# Ex_9BlueLed1RedLedPanel.net
KiCad netlist of a schematic drawn in EAGLE
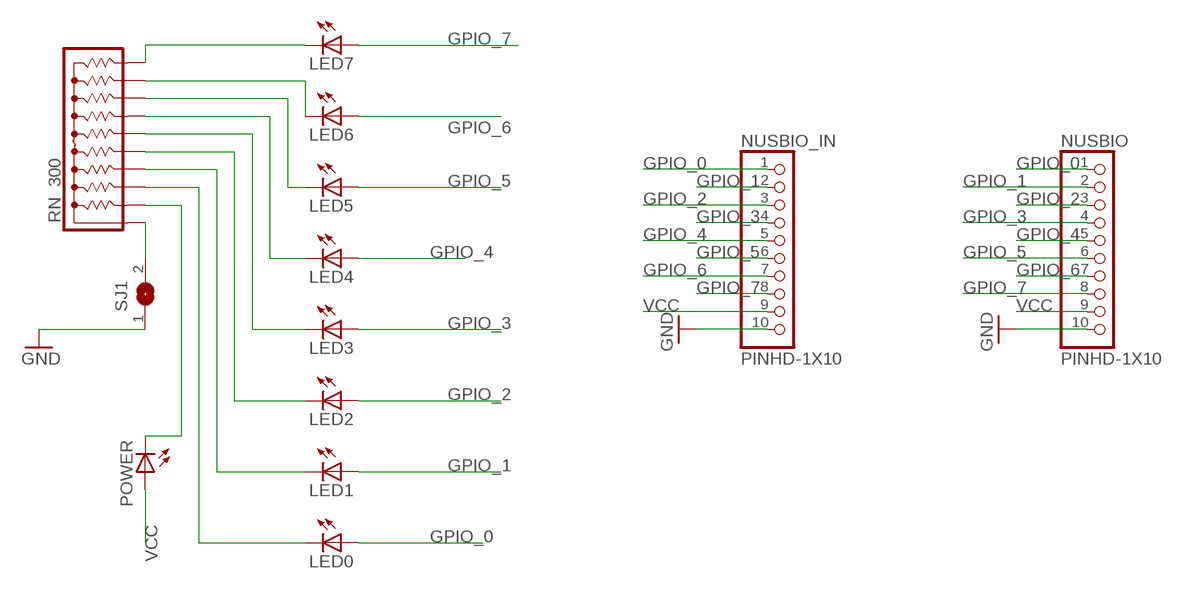
[diagram p0: schematic, sheet 1]

(export (version "E")
  (design (tool "Eeschema 10.0.6"))
  (components
    (comp (ref "LED0")
      (value "LEDSMT1206")
      (footprint "eagle-import:1206")
      (libsource (lib "eagle-import") (part "LEDSMT1206"))
    )
    (comp (ref "LED1")
      (value "LEDSMT1206")
      (footprint "eagle-import:1206")
      (libsource (lib "eagle-import") (part "LEDSMT1206"))
    )
    (comp (ref "LED2")
      (value "LEDSMT1206")
      (footprint "eagle-import:1206")
      (libsource (lib "eagle-import") (part "LEDSMT1206"))
    )
    (comp (ref "LED3")
      (value "LEDSMT1206")
      (footprint "eagle-import:1206")
      (libsource (lib "eagle-import") (part "LEDSMT1206"))
    )
    (comp (ref "LED4")
      (value "LEDSMT1206")
      (footprint "eagle-import:1206")
      (libsource (lib "eagle-import") (part "LEDSMT1206"))
    )
    (comp (ref "LED5")
      (value "LEDSMT1206")
      (footprint "eagle-import:1206")
      (libsource (lib "eagle-import") (part "LEDSMT1206"))
    )
    (comp (ref "LED6")
      (value "LEDSMT1206")
      (footprint "eagle-import:1206")
      (libsource (lib "eagle-import") (part "LEDSMT1206"))
    )
    (comp (ref "LED7")
      (value "LEDSMT1206")
      (footprint "eagle-import:1206")
      (libsource (lib "eagle-import") (part "LEDSMT1206"))
    )
    (comp (ref "NUSBIO")
      (value "PINHD-1X10")
      (footprint "eagle-import:1X10-BIG")
      (libsource (lib "eagle-import") (part "PINHD-1X10"))
    )
    (comp (ref "NUSBIO_IN")
      (value "PINHD-1X10")
      (footprint "eagle-import:1X10-BIG")
      (libsource (lib "eagle-import") (part "PINHD-1X10"))
    )
    (comp (ref "POWER")
      (value "LEDSMT1206")
      (footprint "eagle-import:1206")
      (libsource (lib "eagle-import") (part "LEDSMT1206"))
    )
    (comp (ref "RN_300")
      (value "4610X")
      (footprint "eagle-import:SIP10")
      (libsource (lib "eagle-import") (part "4610X"))
    )
    (comp (ref "SJ1")
      (value "SOLDERJUMPERREFLOW_NOPASTE")
      (footprint "eagle-import:SOLDERJUMPER_REFLOW_NOPASTE")
      (libsource (lib "eagle-import") (part "SOLDERJUMPERREFLOW_NOPASTE"))
    )
  )
  (nets
    (net (code "1") (name "/GPIO_0") (class "Default")
      (node (ref "LED0") (pin "A") (pinfunction "A_A") (pintype "passive"))
      (node (ref "NUSBIO") (pin "1") (pinfunction "1_1") (pintype "passive"))
      (node (ref "NUSBIO_IN") (pin "1") (pinfunction "1_1") (pintype "passive"))
    )
    (net (code "2") (name "/GPIO_1") (class "Default")
      (node (ref "LED1") (pin "A") (pinfunction "A_A") (pintype "passive"))
      (node (ref "NUSBIO") (pin "2") (pinfunction "2_2") (pintype "passive"))
      (node (ref "NUSBIO_IN") (pin "2") (pinfunction "2_2") (pintype "passive"))
    )
    (net (code "3") (name "/GPIO_2") (class "Default")
      (node (ref "LED2") (pin "A") (pinfunction "A_A") (pintype "passive"))
      (node (ref "NUSBIO") (pin "3") (pinfunction "3_3") (pintype "passive"))
      (node (ref "NUSBIO_IN") (pin "3") (pinfunction "3_3") (pintype "passive"))
    )
    (net (code "4") (name "/GPIO_3") (class "Default")
      (node (ref "LED3") (pin "A") (pinfunction "A_A") (pintype "passive"))
      (node (ref "NUSBIO") (pin "4") (pinfunction "4_4") (pintype "passive"))
      (node (ref "NUSBIO_IN") (pin "4") (pinfunction "4_4") (pintype "passive"))
    )
    (net (code "5") (name "/GPIO_4") (class "Default")
      (node (ref "LED4") (pin "A") (pinfunction "A_A") (pintype "passive"))
      (node (ref "NUSBIO") (pin "5") (pinfunction "5_5") (pintype "passive"))
      (node (ref "NUSBIO_IN") (pin "5") (pinfunction "5_5") (pintype "passive"))
    )
    (net (code "6") (name "/GPIO_5") (class "Default")
      (node (ref "LED5") (pin "A") (pinfunction "A_A") (pintype "passive"))
      (node (ref "NUSBIO") (pin "6") (pinfunction "6_6") (pintype "passive"))
      (node (ref "NUSBIO_IN") (pin "6") (pinfunction "6_6") (pintype "passive"))
    )
    (net (code "7") (name "/GPIO_6") (class "Default")
      (node (ref "LED6") (pin "A") (pinfunction "A_A") (pintype "passive"))
      (node (ref "NUSBIO") (pin "7") (pinfunction "7_7") (pintype "passive"))
      (node (ref "NUSBIO_IN") (pin "7") (pinfunction "7_7") (pintype "passive"))
    )
    (net (code "8") (name "/GPIO_7") (class "Default")
      (node (ref "LED7") (pin "A") (pinfunction "A_A") (pintype "passive"))
      (node (ref "NUSBIO") (pin "8") (pinfunction "8_8") (pintype "passive"))
      (node (ref "NUSBIO_IN") (pin "8") (pinfunction "8_8") (pintype "passive"))
    )
    (net (code "9") (name "/VCC") (class "Default")
      (node (ref "NUSBIO") (pin "9") (pinfunction "9_9") (pintype "passive"))
      (node (ref "NUSBIO_IN") (pin "9") (pinfunction "9_9") (pintype "passive"))
      (node (ref "POWER") (pin "A") (pinfunction "A_A") (pintype "passive"))
    )
    (net (code "10") (name "GND") (class "Default")
      (node (ref "NUSBIO") (pin "10") (pinfunction "10_10") (pintype "passive"))
      (node (ref "NUSBIO_IN") (pin "10") (pinfunction "10_10") (pintype "passive"))
      (node (ref "SJ1") (pin "1") (pinfunction "1_1") (pintype "passive"))
    )
    (net (code "11") (name "Net-(LED0-PadC)") (class "Default")
      (node (ref "LED0") (pin "C") (pinfunction "C_C") (pintype "passive"))
      (node (ref "RN_300") (pin "3") (pinfunction "3_3") (pintype "passive"))
    )
    (net (code "12") (name "Net-(LED1-PadC)") (class "Default")
      (node (ref "LED1") (pin "C") (pinfunction "C_C") (pintype "passive"))
      (node (ref "RN_300") (pin "4") (pinfunction "4_4") (pintype "passive"))
    )
    (net (code "13") (name "Net-(LED2-PadC)") (class "Default")
      (node (ref "LED2") (pin "C") (pinfunction "C_C") (pintype "passive"))
      (node (ref "RN_300") (pin "5") (pinfunction "5_5") (pintype "passive"))
    )
    (net (code "14") (name "Net-(LED3-PadC)") (class "Default")
      (node (ref "LED3") (pin "C") (pinfunction "C_C") (pintype "passive"))
      (node (ref "RN_300") (pin "6") (pinfunction "6_6") (pintype "passive"))
    )
    (net (code "15") (name "Net-(LED4-PadC)") (class "Default")
      (node (ref "LED4") (pin "C") (pinfunction "C_C") (pintype "passive"))
      (node (ref "RN_300") (pin "7") (pinfunction "7_7") (pintype "passive"))
    )
    (net (code "16") (name "Net-(LED5-PadC)") (class "Default")
      (node (ref "LED5") (pin "C") (pinfunction "C_C") (pintype "passive"))
      (node (ref "RN_300") (pin "8") (pinfunction "8_8") (pintype "passive"))
    )
    (net (code "17") (name "Net-(LED6-PadC)") (class "Default")
      (node (ref "LED6") (pin "C") (pinfunction "C_C") (pintype "passive"))
      (node (ref "RN_300") (pin "9") (pinfunction "9_9") (pintype "passive"))
    )
    (net (code "18") (name "Net-(LED7-PadC)") (class "Default")
      (node (ref "LED7") (pin "C") (pinfunction "C_C") (pintype "passive"))
      (node (ref "RN_300") (pin "10") (pinfunction "10_10") (pintype "passive"))
    )
    (net (code "19") (name "Net-(POWER-PadC)") (class "Default")
      (node (ref "POWER") (pin "C") (pinfunction "C_C") (pintype "passive"))
      (node (ref "RN_300") (pin "2") (pinfunction "2_2") (pintype "passive"))
    )
    (net (code "20") (name "Net-(RN_300-Pad1)") (class "Default")
      (node (ref "RN_300") (pin "1") (pinfunction "1_1") (pintype "passive"))
      (node (ref "SJ1") (pin "2") (pinfunction "2_2") (pintype "passive"))
    )
  )
)
